# LCDTFTPWR_TPS61040.net
KiCad netlist of a schematic drawn in Altium Designer
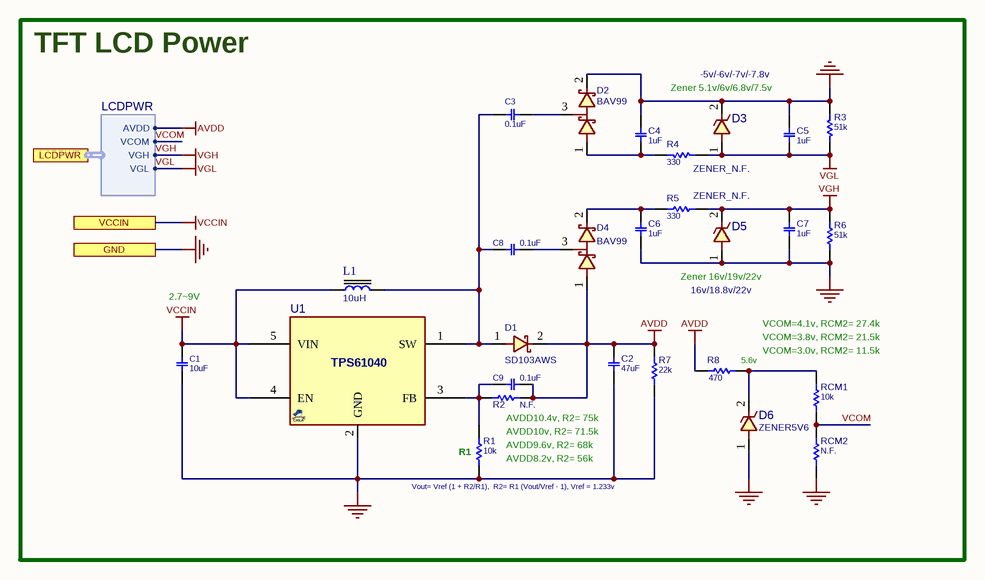
[diagram p0: LCDTFTPWR_TPS61040.SchDoc]

(export (version "E")
  (design (tool "Eeschema 10.0.6"))
  (components
    (comp (ref "C1")
      (value "10uF")
      (footprint "C0402")
      (description "CAP, MLCC")
      (fields (field (name "MANF_P#") "CL10A106MO8NQNC") (field (name "MANF") "Samsung"))
      (libsource (lib "passive_smd") (part "CAP_SMD_MLCC"))
    )
    (comp (ref "C2")
      (value "47uF")
      (footprint "C1206")
      (description "CAP, MLCC")
      (fields (field (name "MANF_P#") "GRM31CR61E476ME44L") (field (name "MANF") "Murata"))
      (libsource (lib "passive_smd") (part "CAP_SMD_MLCC"))
    )
    (comp (ref "C3")
      (value "0.1uF")
      (footprint "C0402")
      (description "CAP, MLCC, 100nF, 50V, X7R, 10%, 0402C")
      (fields (field (name "MANF") "Murata") (field (name "MANF_P#") "GCM155R71H104KE02D"))
      (libsource (lib "passive_mlcc_smd") (part "CAP_SMD_MLCC_100n50V"))
    )
    (comp (ref "C4")
      (value "1uF")
      (footprint "C0603")
      (description "CAP, MLCC")
      (fields (field (name "MANF_P#") "CL10A105KB8NNNC") (field (name "MANF") "Samsung"))
      (libsource (lib "passive_smd") (part "CAP_SMD_MLCC"))
    )
    (comp (ref "C5")
      (value "1uF")
      (footprint "C0603")
      (description "CAP, MLCC")
      (fields (field (name "MANF_P#") "CL10A105KB8NNNC") (field (name "MANF") "Samsung"))
      (libsource (lib "passive_smd") (part "CAP_SMD_MLCC"))
    )
    (comp (ref "C6")
      (value "1uF")
      (footprint "C0603")
      (description "CAP, MLCC")
      (fields (field (name "MANF_P#") "CL10A105KB8NNNC") (field (name "MANF") "Samsung"))
      (libsource (lib "passive_smd") (part "CAP_SMD_MLCC"))
    )
    (comp (ref "C7")
      (value "1uF")
      (footprint "C0603")
      (description "CAP, MLCC")
      (fields (field (name "MANF_P#") "CL10A105KB8NNNC") (field (name "MANF") "Samsung"))
      (libsource (lib "passive_smd") (part "CAP_SMD_MLCC"))
    )
    (comp (ref "C8")
      (value "0.1uF")
      (footprint "C0402")
      (description "CAP, MLCC, 100nF, 50V, X7R, 10%, 0402C")
      (fields (field (name "MANF") "Murata") (field (name "MANF_P#") "GCM155R71H104KE02D"))
      (libsource (lib "passive_mlcc_smd") (part "CAP_SMD_MLCC_100n50V"))
    )
    (comp (ref "C9")
      (value "0.1uF")
      (footprint "C0402")
      (description "CAP, MLCC, 100nF, 50V, X7R, 10%, 0402C")
      (fields (field (name "MANF") "Murata") (field (name "MANF_P#") "GCM155R71H104KE02D"))
      (libsource (lib "passive_mlcc_smd") (part "CAP_SMD_MLCC_100n50V"))
    )
    (comp (ref "D1")
      (value "SD103AWS")
      (footprint "D_SOD323")
      (description "DIODE, SCHOTTKY, 40V, 2A")
      (fields (field (name "MANF") "DIODES"))
      (libsource (lib "diode") (part "DIODE_SMD_SCHOTTKY_1N5819"))
    )
    (comp (ref "D2")
      (value "BAV99")
      (footprint "SOT23_3")
      (description "DIODE, SCHOTTKY, DUAL, 30V, 0.2A")
      (fields (field (name "MANF") "Diodes"))
      (libsource (lib "diode") (part "DIODE_SMD_SCHOTTKY_BAV99"))
    )
    (comp (ref "D3")
      (value "ZENER_N.F.")
      (footprint "D_SOD123W")
      (description "DIODE, ZENER, 0.5W")
      (fields (field (name "MANF") "Diodes"))
      (libsource (lib "diode") (part "DIODE_SMD_ZENER_DFLZ5V1"))
    )
    (comp (ref "D4")
      (value "BAV99")
      (footprint "SOT23_3")
      (description "DIODE, SCHOTTKY, DUAL, 30V, 0.2A")
      (fields (field (name "MANF") "Diodes"))
      (libsource (lib "diode") (part "DIODE_SMD_SCHOTTKY_BAV99"))
    )
    (comp (ref "D5")
      (value "ZENER_N.F.")
      (footprint "D_SOD123W")
      (description "DIODE, ZENER, 0.5W")
      (fields (field (name "MANF") "Diodes"))
      (libsource (lib "diode") (part "DIODE_SMD_ZENER_DFLZ5V1"))
    )
    (comp (ref "D6")
      (value "ZENER5V6")
      (footprint "D_SOD123W")
      (description "DIODE, ZENER, 0.5W")
      (fields (field (name "MANF") "Diodes"))
      (libsource (lib "diode") (part "DIODE_SMD_ZENER_DFLZ5V1"))
    )
    (comp (ref "L1")
      (value "10uH")
      (footprint "L_4")
      (description "INDUCTOR, POWER, SMD")
      (fields (field (name "MANF_P#") "GCD43-100MC"))
      (libsource (lib "passive") (part "INDPWR_SMD"))
    )
    (comp (ref "R1")
      (value "10k")
      (footprint "R0402")
      (description "RESISTOR, SMD, 20K, 0402")
      (fields (field (name "MANF") "Yageo") (field (name "MANF_P#") "RK73H1ETTP2002F"))
      (libsource (lib "chila_passive") (part "RES_SMD"))
    )
    (comp (ref "R2")
      (value "N.F.")
      (footprint "R0402")
      (description "RESISTOR, SMD, 20K, 0402")
      (fields (field (name "MANF") "Yageo") (field (name "MANF_P#") "RK73H1ETTP2002F"))
      (libsource (lib "chila_passive") (part "RES_SMD"))
    )
    (comp (ref "R3")
      (value "51k")
      (footprint "R0402")
      (description "RESISTOR, SMD, 20K, 0402")
      (fields (field (name "MANF") "Yageo") (field (name "MANF_P#") "RK73H1ETTP2002F"))
      (libsource (lib "chila_passive") (part "RES_SMD"))
    )
    (comp (ref "R4")
      (value "330")
      (footprint "R0402")
      (description "RESISTOR, SMD, 20K, 0402")
      (fields (field (name "MANF") "Yageo") (field (name "MANF_P#") "RK73H1ETTP2002F"))
      (libsource (lib "chila_passive") (part "RES_SMD"))
    )
    (comp (ref "R5")
      (value "330")
      (footprint "R0402")
      (description "RESISTOR, SMD, 20K, 0402")
      (fields (field (name "MANF") "Yageo") (field (name "MANF_P#") "RK73H1ETTP2002F"))
      (libsource (lib "chila_passive") (part "RES_SMD"))
    )
    (comp (ref "R6")
      (value "51k")
      (footprint "R0402")
      (description "RESISTOR, SMD, 20K, 0402")
      (fields (field (name "MANF") "Yageo") (field (name "MANF_P#") "RK73H1ETTP2002F"))
      (libsource (lib "chila_passive") (part "RES_SMD"))
    )
    (comp (ref "R7")
      (value "22k")
      (footprint "R0402")
      (description "RESISTOR, SMD, 20K, 0402")
      (fields (field (name "MANF") "Yageo") (field (name "MANF_P#") "RK73H1ETTP2002F"))
      (libsource (lib "chila_passive") (part "RES_SMD"))
    )
    (comp (ref "R8")
      (value "470")
      (footprint "R0402")
      (description "RESISTOR, SMD, 20K, 0402")
      (fields (field (name "MANF") "Yageo") (field (name "MANF_P#") "RK73H1ETTP2002F"))
      (libsource (lib "chila_passive") (part "RES_SMD"))
    )
    (comp (ref "RCM1")
      (value "10k")
      (footprint "R0402")
      (description "RESISTOR, SMD, 20K, 0402")
      (fields (field (name "MANF") "Yageo") (field (name "MANF_P#") "RK73H1ETTP2002F"))
      (libsource (lib "chila_passive") (part "RES_SMD"))
    )
    (comp (ref "RCM2")
      (value "N.F.")
      (footprint "R0402")
      (description "RESISTOR, SMD, 20K, 0402")
      (fields (field (name "MANF") "Yageo") (field (name "MANF_P#") "RK73H1ETTP2002F"))
      (libsource (lib "chila_passive") (part "RES_SMD"))
    )
    (comp (ref "U1")
      (value "TPS61040")
      (footprint "SOT23_5")
      (description "REG, Switching, Boost, 0.4A, ADJ, 1MHz, SOT-23-5")
      (fields (field (name "MANF_P#") "TPS61040DBVR") (field (name "MANF") "TI"))
      (libsource (lib "pwr_switching_boost") (part "VREG_TPS61040_SOT23"))
    )
  )
  (nets
    (net (code "2") (name "/VCOM") (class "Default")
      (node (ref "RCM1") (pin "2") (pinfunction "2_2") (pintype "passive"))
      (node (ref "RCM2") (pin "1") (pinfunction "1_1") (pintype "passive"))
    )
    (net (code "4") (name "AVDD") (class "Default")
      (node (ref "C2") (pin "2") (pinfunction "2_2") (pintype "passive"))
      (node (ref "C9") (pin "1") (pinfunction "1_1") (pintype "passive"))
      (node (ref "D1") (pin "2") (pinfunction "2_2") (pintype "passive"))
      (node (ref "D4") (pin "1") (pinfunction "1_1") (pintype "passive"))
      (node (ref "R2") (pin "2") (pinfunction "2_2") (pintype "passive"))
      (node (ref "R7") (pin "1") (pinfunction "1_1") (pintype "passive"))
      (node (ref "R8") (pin "1") (pinfunction "1_1") (pintype "passive"))
    )
    (net (code "5") (name "GND") (class "Default")
      (node (ref "C1") (pin "1") (pinfunction "1_1") (pintype "passive"))
      (node (ref "C2") (pin "1") (pinfunction "1_1") (pintype "passive"))
      (node (ref "C4") (pin "1") (pinfunction "1_1") (pintype "passive"))
      (node (ref "C5") (pin "1") (pinfunction "1_1") (pintype "passive"))
      (node (ref "C6") (pin "1") (pinfunction "1_1") (pintype "passive"))
      (node (ref "C7") (pin "1") (pinfunction "1_1") (pintype "passive"))
      (node (ref "D2") (pin "2") (pinfunction "2_2") (pintype "passive"))
      (node (ref "D3") (pin "2") (pinfunction "2_2") (pintype "passive"))
      (node (ref "D5") (pin "1") (pinfunction "1_1") (pintype "passive"))
      (node (ref "D6") (pin "1") (pinfunction "1_1") (pintype "passive"))
      (node (ref "R1") (pin "2") (pinfunction "2_2") (pintype "passive"))
      (node (ref "R3") (pin "1") (pinfunction "1_1") (pintype "passive"))
      (node (ref "R6") (pin "1") (pinfunction "1_1") (pintype "passive"))
      (node (ref "R7") (pin "2") (pinfunction "2_2") (pintype "passive"))
      (node (ref "RCM2") (pin "2") (pinfunction "2_2") (pintype "passive"))
      (node (ref "U1") (pin "2") (pinfunction "GND_2") (pintype "tri_state"))
    )
    (net (code "6") (name "Net-(C3-Pad1)") (class "Default")
      (node (ref "C3") (pin "1") (pinfunction "1_1") (pintype "passive"))
      (node (ref "D2") (pin "3") (pinfunction "3_3") (pintype "passive"))
    )
    (net (code "7") (name "Net-(C4-Pad2)") (class "Default")
      (node (ref "C4") (pin "2") (pinfunction "2_2") (pintype "passive"))
      (node (ref "D2") (pin "1") (pinfunction "1_1") (pintype "passive"))
      (node (ref "R4") (pin "1") (pinfunction "1_1") (pintype "passive"))
    )
    (net (code "8") (name "Net-(C6-Pad2)") (class "Default")
      (node (ref "C6") (pin "2") (pinfunction "2_2") (pintype "passive"))
      (node (ref "D4") (pin "2") (pinfunction "2_2") (pintype "passive"))
      (node (ref "R5") (pin "1") (pinfunction "1_1") (pintype "passive"))
    )
    (net (code "9") (name "Net-(C8-Pad1)") (class "Default")
      (node (ref "C8") (pin "1") (pinfunction "1_1") (pintype "passive"))
      (node (ref "D4") (pin "3") (pinfunction "3_3") (pintype "passive"))
    )
    (net (code "10") (name "Net-(D6-Pad2)") (class "Default")
      (node (ref "D6") (pin "2") (pinfunction "2_2") (pintype "passive"))
      (node (ref "R8") (pin "2") (pinfunction "2_2") (pintype "passive"))
      (node (ref "RCM1") (pin "1") (pinfunction "1_1") (pintype "passive"))
    )
    (net (code "11") (name "Net-(U1-FB)") (class "Default")
      (node (ref "C9") (pin "2") (pinfunction "2_2") (pintype "passive"))
      (node (ref "R1") (pin "1") (pinfunction "1_1") (pintype "passive"))
      (node (ref "R2") (pin "1") (pinfunction "1_1") (pintype "passive"))
      (node (ref "U1") (pin "3") (pinfunction "FB_3") (pintype "tri_state"))
    )
    (net (code "12") (name "Net-(U1-SW)") (class "Default")
      (node (ref "C3") (pin "2") (pinfunction "2_2") (pintype "passive"))
      (node (ref "C8") (pin "2") (pinfunction "2_2") (pintype "passive"))
      (node (ref "D1") (pin "1") (pinfunction "1_1") (pintype "passive"))
      (node (ref "L1") (pin "2") (pinfunction "2_2") (pintype "passive"))
      (node (ref "U1") (pin "1") (pinfunction "SW_1") (pintype "tri_state"))
    )
    (net (code "13") (name "VCCIN") (class "Default")
      (node (ref "C1") (pin "2") (pinfunction "2_2") (pintype "passive"))
      (node (ref "L1") (pin "1") (pinfunction "1_1") (pintype "passive"))
      (node (ref "U1") (pin "4") (pinfunction "EN_4") (pintype "tri_state"))
      (node (ref "U1") (pin "5") (pinfunction "VIN_5") (pintype "tri_state"))
    )
    (net (code "14") (name "VGH") (class "Default")
      (node (ref "C7") (pin "2") (pinfunction "2_2") (pintype "passive"))
      (node (ref "D5") (pin "2") (pinfunction "2_2") (pintype "passive"))
      (node (ref "R5") (pin "2") (pinfunction "2_2") (pintype "passive"))
      (node (ref "R6") (pin "2") (pinfunction "2_2") (pintype "passive"))
    )
    (net (code "15") (name "VGL") (class "Default")
      (node (ref "C5") (pin "2") (pinfunction "2_2") (pintype "passive"))
      (node (ref "D3") (pin "1") (pinfunction "1_1") (pintype "passive"))
      (node (ref "R3") (pin "2") (pinfunction "2_2") (pintype "passive"))
      (node (ref "R4") (pin "2") (pinfunction "2_2") (pintype "passive"))
    )
  )
)
